# rfm69.net
KiCad netlist of a schematic drawn in EAGLE
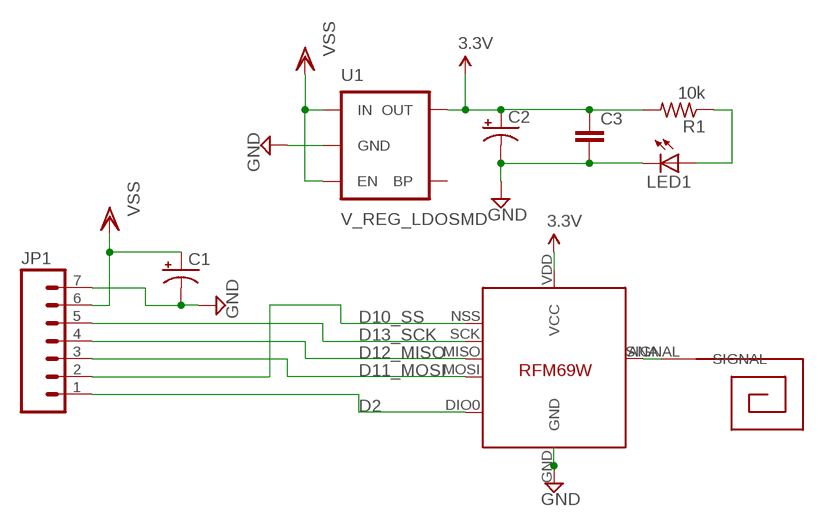
[diagram p0: schematic, sheet 1]

(export (version "E")
  (design (tool "Eeschema 10.0.6"))
  (components
    (comp (ref "C1")
      (value "CAP_POL1206")
      (footprint "eagle-import:EIA3216")
      (libsource (lib "eagle-import") (part "CAP_POL1206"))
    )
    (comp (ref "C2")
      (value "CAP_POL1206")
      (footprint "eagle-import:EIA3216")
      (libsource (lib "eagle-import") (part "CAP_POL1206"))
    )
    (comp (ref "C3")
      (value "CAP0603-CAP")
      (footprint "eagle-import:0603-CAP")
      (libsource (lib "eagle-import") (part "CAP0603-CAP"))
    )
    (comp (ref "JP1")
      (value "M07LONGPADS")
      (footprint "eagle-import:1X07_LONGPADS")
      (libsource (lib "eagle-import") (part "M07LONGPADS"))
    )
    (comp (ref "LED1")
      (value "LEDCHIP-LED0603")
      (footprint "eagle-import:CHIP-LED0603")
      (libsource (lib "eagle-import") (part "LEDCHIP-LED0603"))
    )
    (comp (ref "R1")
      (value "10k")
      (footprint "eagle-import:R0603")
      (libsource (lib "eagle-import") (part "R-US_R0603"))
    )
    (comp (ref "U$1")
      (value "915MHZ-ANTENNA-SMD")
      (footprint "eagle-import:915MHZ-ANTENNA")
      (libsource (lib "eagle-import") (part "915MHZ-ANTENNA-SMD"))
    )
    (comp (ref "U$5")
      (value "RFM69")
      (footprint "eagle-import:RFM69W-MINPADS")
      (libsource (lib "eagle-import") (part "RFM69"))
    )
    (comp (ref "U1")
      (value "V_REG_LDOSMD")
      (footprint "eagle-import:SOT23-5")
      (libsource (lib "eagle-import") (part "V_REG_LDOSMD"))
    )
  )
  (nets
    (net (code "1") (name "/D2") (class "Default")
      (node (ref "JP1") (pin "1") (pinfunction "1_1") (pintype "passive"))
      (node (ref "U$5") (pin "DIO0") (pinfunction "DIO0_DIO0") (pintype "open_collector"))
    )
    (net (code "2") (name "/D10_SS") (class "Default")
      (node (ref "JP1") (pin "2") (pinfunction "2_2") (pintype "passive"))
      (node (ref "U$5") (pin "NSS") (pinfunction "SEL_NSS") (pintype "input"))
    )
    (net (code "3") (name "/D11_MOSI") (class "Default")
      (node (ref "JP1") (pin "3") (pinfunction "3_3") (pintype "passive"))
      (node (ref "U$5") (pin "MOSI") (pinfunction "MOSI_MOSI") (pintype "output"))
    )
    (net (code "4") (name "/D12_MISO") (class "Default")
      (node (ref "JP1") (pin "4") (pinfunction "4_4") (pintype "passive"))
      (node (ref "U$5") (pin "MISO") (pinfunction "MISO_MISO") (pintype "input"))
    )
    (net (code "5") (name "/D13_SCK") (class "Default")
      (node (ref "JP1") (pin "5") (pinfunction "5_5") (pintype "passive"))
      (node (ref "U$5") (pin "SCK") (pinfunction "SCK_SCK") (pintype "input"))
    )
    (net (code "6") (name "3.3V") (class "Default")
      (node (ref "C2") (pin "A") (pinfunction "+_A") (pintype "passive"))
      (node (ref "C3") (pin "1") (pinfunction "1_1") (pintype "passive"))
      (node (ref "R1") (pin "2") (pinfunction "2_2") (pintype "passive"))
      (node (ref "U$5") (pin "VDD") (pinfunction "VCC_VDD") (pintype "power_in"))
      (node (ref "U1") (pin "5") (pinfunction "OUT_5") (pintype "passive"))
    )
    (net (code "7") (name "GND") (class "Default")
      (node (ref "C1") (pin "C") (pinfunction "-_C") (pintype "passive"))
      (node (ref "C2") (pin "C") (pinfunction "-_C") (pintype "passive"))
      (node (ref "C3") (pin "2") (pinfunction "2_2") (pintype "passive"))
      (node (ref "JP1") (pin "7") (pinfunction "7_7") (pintype "passive"))
      (node (ref "LED1") (pin "C") (pinfunction "C_C") (pintype "passive"))
      (node (ref "U$5") (pin "GND") (pinfunction "GND_GND") (pintype "power_in"))
      (node (ref "U1") (pin "2") (pinfunction "GND_2") (pintype "input"))
    )
    (net (code "8") (name "Net-(LED1-PadA)") (class "Default")
      (node (ref "LED1") (pin "A") (pinfunction "A_A") (pintype "passive"))
      (node (ref "R1") (pin "1") (pinfunction "1_1") (pintype "passive"))
    )
    (net (code "9") (name "Net-(U$5-ANT)") (class "Default")
      (node (ref "U$1") (pin "SIGNAL") (pinfunction "SIGNAL_SIGNAL") (pintype "bidirectional"))
      (node (ref "U$5") (pin "ANA") (pinfunction "ANT_ANA") (pintype "passive"))
    )
    (net (code "10") (name "VSS") (class "Default")
      (node (ref "C1") (pin "A") (pinfunction "+_A") (pintype "passive"))
      (node (ref "JP1") (pin "6") (pinfunction "6_6") (pintype "passive"))
      (node (ref "U1") (pin "1") (pinfunction "IN_1") (pintype "input"))
      (node (ref "U1") (pin "3") (pinfunction "EN_3") (pintype "input"))
    )
    (net (code "11") (name "unconnected-(U1-BP-Pad4)") (class "Default")
      (node (ref "U1") (pin "4") (pinfunction "BP_4") (pintype "input"))
    )
  )
)
